# SAM_E54_Xplained_Pro_Memory.net
KiCad netlist of a schematic drawn in Altium Designer
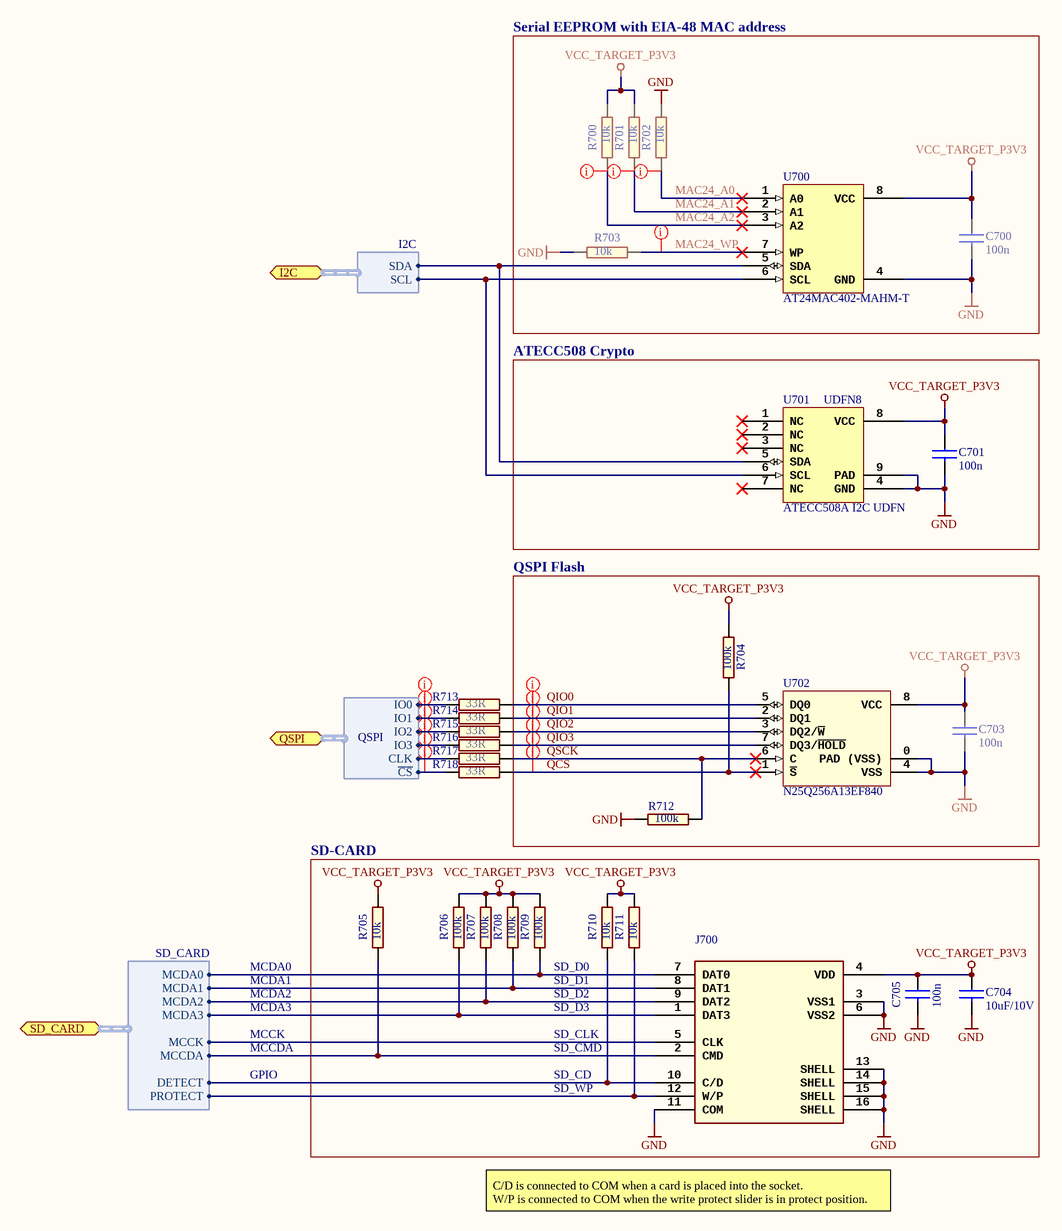
[diagram p0: SAM_E54_Xplained_Pro_Memory.SchDoc]

(export (version "E")
  (design (tool "Eeschema 10.0.6"))
  (components
    (comp (ref "C700")
      (value "100n")
      (footprint "AP1-00053")
      (description "Ceramic capacitor, SMD 0402, X7R, 16V, +/-10%")
      (fields (field (name "TOLERANCE") "16V, +/-10%") (field (name "MANUFACTURER") "Kemet"))
      (libsource (lib "AltiumDbLib") (part "CAP-NONPOL"))
    )
    (comp (ref "C701")
      (value "100n")
      (footprint "AP1-00053")
      (description "Ceramic capacitor, SMD 0402, X7R, 16V, +/-10%")
      (fields (field (name "TOLERANCE") "16V, +/-10%") (field (name "MANUFACTURER") "Kemet"))
      (libsource (lib "AltiumDbLib") (part "CAP-NONPOL"))
    )
    (comp (ref "C703")
      (value "100n")
      (footprint "AP1-00053")
      (description "Ceramic capacitor, SMD 0402, X7R, 16V, +/-10%")
      (fields (field (name "TOLERANCE") "16V, +/-10%") (field (name "MANUFACTURER") "Kemet"))
      (libsource (lib "AltiumDbLib") (part "CAP-NONPOL"))
    )
    (comp (ref "C704")
      (value "10uF/10V")
      (footprint "AP1-00117")
      (description "Ceramic capacitor, SMD 0603, X5R, 10V, 10UF Â± 20%")
      (fields (field (name "MANUFACTURER") "AVX") (field (name "MPN") "0603ZD106MAT2A"))
      (libsource (lib "AltiumDbLib") (part "CAP-NONPOL"))
    )
    (comp (ref "C705")
      (value "100n")
      (footprint "AP1-00053")
      (description "Ceramic capacitor, SMD 0402, X7R, 16V, +/-10%")
      (fields (field (name "TOLERANCE") "16V, +/-10%") (field (name "MANUFACTURER") "Kemet"))
      (libsource (lib "AltiumDbLib") (part "CAP-NONPOL"))
    )
    (comp (ref "J700")
      (value "~")
      (footprint "AP8-00377")
      (description "SD/MMC socket, 2.7mm, push-push, SMD")
      (fields
        (field (name "MANUFACTURER") "Kyocera-elco")
        (field (name "MPN") "KYOCERA - 14 5738 009 220 859+")
      )
      (libsource (lib "AltiumDbLib") (part "SD_MMC"))
    )
    (comp (ref "R700")
      (value "10k")
      (footprint "AP2-00011")
      (description "Thick film resistor, SMD 0402, 1/16W, 1%")
      (fields (field (name "TOLERANCE") "1 %") (field (name "MANUFACTURER") "vishay"))
      (libsource (lib "") (part "R2_1"))
    )
    (comp (ref "R701")
      (value "10k")
      (footprint "AP2-00011")
      (description "Thick film resistor, SMD 0402, 1/16W, 1%")
      (fields (field (name "TOLERANCE") "1 %") (field (name "MANUFACTURER") "vishay"))
      (libsource (lib "") (part "R2_1"))
    )
    (comp (ref "R702")
      (value "10k")
      (footprint "AP2-00011")
      (description "Thick film resistor, SMD 0402, 1/16W, 1%")
      (fields (field (name "TOLERANCE") "1 %") (field (name "MANUFACTURER") "vishay"))
      (libsource (lib "") (part "R2_1"))
    )
    (comp (ref "R703")
      (value "10k")
      (footprint "AP2-00011")
      (description "Thick film resistor, SMD 0402, 1/16W, 1%")
      (fields (field (name "TOLERANCE") "1 %") (field (name "MANUFACTURER") "vishay"))
      (libsource (lib "") (part "R2_2"))
    )
    (comp (ref "R704")
      (value "100k")
      (footprint "AP2-00011")
      (description "Thick film resistor, SMD 0402, 1/16W, 1%")
      (fields (field (name "TOLERANCE") "1 %") (field (name "MANUFACTURER") "ASJ"))
      (libsource (lib "") (part "R2_1"))
    )
    (comp (ref "R705")
      (value "10k")
      (footprint "AP2-00011")
      (description "Thick film resistor, SMD 0402, 1/16W, 1%")
      (fields (field (name "TOLERANCE") "1 %") (field (name "MANUFACTURER") "vishay"))
      (libsource (lib "") (part "R2_1"))
    )
    (comp (ref "R706")
      (value "100k")
      (footprint "AP2-00011")
      (description "Thick film resistor, SMD 0402, 1/16W, 1%")
      (fields (field (name "TOLERANCE") "1 %") (field (name "MANUFACTURER") "ASJ"))
      (libsource (lib "") (part "R2_1"))
    )
    (comp (ref "R707")
      (value "100k")
      (footprint "AP2-00011")
      (description "Thick film resistor, SMD 0402, 1/16W, 1%")
      (fields (field (name "TOLERANCE") "1 %") (field (name "MANUFACTURER") "ASJ"))
      (libsource (lib "") (part "R2_1"))
    )
    (comp (ref "R708")
      (value "100k")
      (footprint "AP2-00011")
      (description "Thick film resistor, SMD 0402, 1/16W, 1%")
      (fields (field (name "TOLERANCE") "1 %") (field (name "MANUFACTURER") "ASJ"))
      (libsource (lib "") (part "R2_1"))
    )
    (comp (ref "R709")
      (value "100k")
      (footprint "AP2-00011")
      (description "Thick film resistor, SMD 0402, 1/16W, 1%")
      (fields (field (name "TOLERANCE") "1 %") (field (name "MANUFACTURER") "ASJ"))
      (libsource (lib "") (part "R2_1"))
    )
    (comp (ref "R710")
      (value "10k")
      (footprint "AP2-00011")
      (description "Thick film resistor, SMD 0402, 1/16W, 1%")
      (fields (field (name "TOLERANCE") "1 %") (field (name "MANUFACTURER") "vishay"))
      (libsource (lib "") (part "R2_1"))
    )
    (comp (ref "R711")
      (value "10k")
      (footprint "AP2-00011")
      (description "Thick film resistor, SMD 0402, 1/16W, 1%")
      (fields (field (name "TOLERANCE") "1 %") (field (name "MANUFACTURER") "vishay"))
      (libsource (lib "") (part "R2_1"))
    )
    (comp (ref "R712")
      (value "100k")
      (footprint "AP2-00011")
      (description "Thick film resistor, SMD 0402, 1/16W, 1%")
      (fields (field (name "TOLERANCE") "1 %") (field (name "MANUFACTURER") "ASJ"))
      (libsource (lib "") (part "R2_2"))
    )
    (comp (ref "R713")
      (value "33R")
      (footprint "AP2-00011")
      (description "Thick film resistor, SMD 0402, 1/16W, 1%")
      (fields (field (name "TOLERANCE") "1 %") (field (name "MANUFACTURER") "ASJ"))
      (libsource (lib "AltiumDbLib") (part "R2"))
    )
    (comp (ref "R714")
      (value "33R")
      (footprint "AP2-00011")
      (description "Thick film resistor, SMD 0402, 1/16W, 1%")
      (fields (field (name "TOLERANCE") "1 %") (field (name "MANUFACTURER") "ASJ"))
      (libsource (lib "AltiumDbLib") (part "R2"))
    )
    (comp (ref "R715")
      (value "33R")
      (footprint "AP2-00011")
      (description "Thick film resistor, SMD 0402, 1/16W, 1%")
      (fields (field (name "TOLERANCE") "1 %") (field (name "MANUFACTURER") "ASJ"))
      (libsource (lib "AltiumDbLib") (part "R2"))
    )
    (comp (ref "R716")
      (value "33R")
      (footprint "AP2-00011")
      (description "Thick film resistor, SMD 0402, 1/16W, 1%")
      (fields (field (name "TOLERANCE") "1 %") (field (name "MANUFACTURER") "ASJ"))
      (libsource (lib "AltiumDbLib") (part "R2"))
    )
    (comp (ref "R717")
      (value "33R")
      (footprint "AP2-00011")
      (description "Thick film resistor, SMD 0402, 1/16W, 1%")
      (fields (field (name "TOLERANCE") "1 %") (field (name "MANUFACTURER") "ASJ"))
      (libsource (lib "AltiumDbLib") (part "R2"))
    )
    (comp (ref "R718")
      (value "33R")
      (footprint "AP2-00011")
      (description "Thick film resistor, SMD 0402, 1/16W, 1%")
      (fields (field (name "TOLERANCE") "1 %") (field (name "MANUFACTURER") "ASJ"))
      (libsource (lib "AltiumDbLib") (part "R2"))
    )
    (comp (ref "U700")
      (value "AT24MAC402-MAHM-T")
      (footprint "AP6-00186")
      (description "2kbit I2C EEPROM, single EUI-48 MAC, 1.7-5.5V, 2x3mm UDFN (8MA2)")
      (fields (field (name "MANUFACTURER") "ATMEL"))
      (libsource (lib "AltiumDbLib") (part "AT24MAC-8PIN"))
    )
    (comp (ref "U701")
      (value "ATECC508A I2C UDFN")
      (footprint "AP6-00409")
      (description "ATECC508A with an I2C Interface and a 8 Pin UDFN Package with Paddle")
      (fields (field (name "MANUFACTURER") "MICROCHIP") (field (name "MPN") "ATECC508A-MAHDA-T"))
      (libsource (lib "AltiumDbLib") (part "ATECC508A_I2C_UDFN"))
    )
    (comp (ref "U702")
      (value "N25Q256A13EF840")
      (footprint "AP6-00478")
      (description "256 Mbit (32MB) QSPI flash, 3.3V, 108MHz, V-PDFN-8 (8x6mm)")
      (fields (field (name "MANUFACTURER") "Micron") (field (name "MPN") "N25Q256A13EF840F"))
      (libsource (lib "AltiumDbLib") (part "N25Q256A1"))
    )
  )
  (nets
    (net (code "4") (name "/CLK") (class "Default")
      (node (ref "R717") (pin "2") (pinfunction "2_2") (pintype "passive"))
    )
    (net (code "5") (name "/DETECT") (class "Default")
      (node (ref "J700") (pin "10") (pinfunction "C/D_10") (pintype "passive"))
      (node (ref "R710") (pin "1") (pinfunction "1_1") (pintype "passive"))
    )
    (net (code "6") (name "/IO0") (class "Default")
      (node (ref "R713") (pin "2") (pinfunction "2_2") (pintype "passive"))
    )
    (net (code "7") (name "/IO1") (class "Default")
      (node (ref "R714") (pin "2") (pinfunction "2_2") (pintype "passive"))
    )
    (net (code "8") (name "/IO2") (class "Default")
      (node (ref "R715") (pin "2") (pinfunction "2_2") (pintype "passive"))
    )
    (net (code "9") (name "/IO3") (class "Default")
      (node (ref "R716") (pin "2") (pinfunction "2_2") (pintype "passive"))
    )
    (net (code "10") (name "/MAC24_A0") (class "Default")
      (node (ref "R702") (pin "1") (pinfunction "1_1") (pintype "passive"))
      (node (ref "U700") (pin "1") (pinfunction "A0_1") (pintype "input"))
    )
    (net (code "11") (name "/MAC24_A1") (class "Default")
      (node (ref "R701") (pin "1") (pinfunction "1_1") (pintype "passive"))
      (node (ref "U700") (pin "2") (pinfunction "A1_2") (pintype "input"))
    )
    (net (code "12") (name "/MAC24_A2") (class "Default")
      (node (ref "R700") (pin "1") (pinfunction "1_1") (pintype "passive"))
      (node (ref "U700") (pin "3") (pinfunction "A2_3") (pintype "input"))
    )
    (net (code "13") (name "/MAC24_WP") (class "Default")
      (node (ref "R703") (pin "2") (pinfunction "2_2") (pintype "passive"))
      (node (ref "U700") (pin "7") (pinfunction "WP_7") (pintype "input"))
    )
    (net (code "14") (name "/MCCDA") (class "Default")
      (node (ref "J700") (pin "2") (pinfunction "CMD_2") (pintype "passive"))
      (node (ref "R705") (pin "1") (pinfunction "1_1") (pintype "passive"))
    )
    (net (code "15") (name "/MCCK") (class "Default")
      (node (ref "J700") (pin "5") (pinfunction "CLK_5") (pintype "passive"))
    )
    (net (code "16") (name "/MCDA0") (class "Default")
      (node (ref "J700") (pin "7") (pinfunction "DAT0_7") (pintype "passive"))
      (node (ref "R709") (pin "1") (pinfunction "1_1") (pintype "passive"))
    )
    (net (code "17") (name "/MCDA1") (class "Default")
      (node (ref "J700") (pin "8") (pinfunction "DAT1_8") (pintype "passive"))
      (node (ref "R708") (pin "1") (pinfunction "1_1") (pintype "passive"))
    )
    (net (code "18") (name "/MCDA2") (class "Default")
      (node (ref "J700") (pin "9") (pinfunction "DAT2_9") (pintype "passive"))
      (node (ref "R707") (pin "1") (pinfunction "1_1") (pintype "passive"))
    )
    (net (code "19") (name "/MCDA3") (class "Default")
      (node (ref "J700") (pin "1") (pinfunction "DAT3_1") (pintype "passive"))
      (node (ref "R706") (pin "1") (pinfunction "1_1") (pintype "passive"))
    )
    (net (code "20") (name "/PROTECT") (class "Default")
      (node (ref "J700") (pin "12") (pinfunction "W/P_12") (pintype "passive"))
      (node (ref "R711") (pin "1") (pinfunction "1_1") (pintype "passive"))
    )
    (net (code "21") (name "/QCS") (class "Default")
      (node (ref "R704") (pin "1") (pinfunction "1_1") (pintype "passive"))
      (node (ref "R718") (pin "1") (pinfunction "1_1") (pintype "passive"))
      (node (ref "U702") (pin "1") (pinfunction "~{S}_1") (pintype "input"))
    )
    (net (code "22") (name "/QIO0") (class "Default")
      (node (ref "R713") (pin "1") (pinfunction "1_1") (pintype "passive"))
      (node (ref "U702") (pin "5") (pinfunction "DQ0_5") (pintype "bidirectional"))
    )
    (net (code "23") (name "/QIO1") (class "Default")
      (node (ref "R714") (pin "1") (pinfunction "1_1") (pintype "passive"))
      (node (ref "U702") (pin "2") (pinfunction "DQ1_2") (pintype "bidirectional"))
    )
    (net (code "24") (name "/QIO2") (class "Default")
      (node (ref "R715") (pin "1") (pinfunction "1_1") (pintype "passive"))
      (node (ref "U702") (pin "3") (pinfunction "DQ2/~{W}_3") (pintype "bidirectional"))
    )
    (net (code "25") (name "/QIO3") (class "Default")
      (node (ref "R716") (pin "1") (pinfunction "1_1") (pintype "passive"))
      (node (ref "U702") (pin "7") (pinfunction "DQ3/~{HOLD}_7") (pintype "bidirectional"))
    )
    (net (code "26") (name "/QSCK") (class "Default")
      (node (ref "R712") (pin "2") (pinfunction "2_2") (pintype "passive"))
      (node (ref "R717") (pin "1") (pinfunction "1_1") (pintype "passive"))
      (node (ref "U702") (pin "6") (pinfunction "C_6") (pintype "input"))
    )
    (net (code "27") (name "/SCL") (class "Default")
      (node (ref "U700") (pin "6") (pinfunction "SCL_6") (pintype "input"))
      (node (ref "U701") (pin "6") (pinfunction "SCL_6") (pintype "input"))
    )
    (net (code "28") (name "/SDA") (class "Default")
      (node (ref "U700") (pin "5") (pinfunction "SDA_5") (pintype "bidirectional"))
      (node (ref "U701") (pin "5") (pinfunction "SDA_5") (pintype "bidirectional"))
    )
    (net (code "32") (name "/~{CS}") (class "Default")
      (node (ref "R718") (pin "2") (pinfunction "2_2") (pintype "passive"))
    )
    (net (code "33") (name "GND") (class "Default")
      (node (ref "C700") (pin "2") (pinfunction "2_2") (pintype "passive"))
      (node (ref "C701") (pin "2") (pinfunction "2_2") (pintype "passive"))
      (node (ref "C703") (pin "2") (pinfunction "2_2") (pintype "passive"))
      (node (ref "C704") (pin "2") (pinfunction "2_2") (pintype "passive"))
      (node (ref "C705") (pin "2") (pinfunction "2_2") (pintype "passive"))
      (node (ref "J700") (pin "11") (pinfunction "COM_11") (pintype "passive"))
      (node (ref "J700") (pin "13") (pinfunction "SHELL_13") (pintype "passive"))
      (node (ref "J700") (pin "14") (pinfunction "SHELL_14") (pintype "passive"))
      (node (ref "J700") (pin "15") (pinfunction "SHELL_15") (pintype "passive"))
      (node (ref "J700") (pin "16") (pinfunction "SHELL_16") (pintype "passive"))
      (node (ref "J700") (pin "3") (pinfunction "VSS1_3") (pintype "passive"))
      (node (ref "J700") (pin "6") (pinfunction "VSS2_6") (pintype "passive"))
      (node (ref "R702") (pin "2") (pinfunction "2_2") (pintype "passive"))
      (node (ref "R703") (pin "1") (pinfunction "1_1") (pintype "passive"))
      (node (ref "R712") (pin "1") (pinfunction "1_1") (pintype "passive"))
      (node (ref "U700") (pin "4") (pinfunction "GND_4") (pintype "power_in"))
      (node (ref "U701") (pin "4") (pinfunction "GND_4") (pintype "power_in"))
      (node (ref "U701") (pin "9") (pinfunction "PAD_9") (pintype "power_in"))
      (node (ref "U702") (pin "0") (pinfunction "PAD_(VSS)_0") (pintype "power_in"))
      (node (ref "U702") (pin "4") (pinfunction "VSS_4") (pintype "power_in"))
    )
    (net (code "34") (name "VCC_TARGET_P3V3") (class "Default")
      (node (ref "C700") (pin "1") (pinfunction "1_1") (pintype "passive"))
      (node (ref "C701") (pin "1") (pinfunction "1_1") (pintype "passive"))
      (node (ref "C703") (pin "1") (pinfunction "1_1") (pintype "passive"))
      (node (ref "C704") (pin "1") (pinfunction "1_1") (pintype "passive"))
      (node (ref "C705") (pin "1") (pinfunction "1_1") (pintype "passive"))
      (node (ref "J700") (pin "4") (pinfunction "VDD_4") (pintype "passive"))
      (node (ref "R700") (pin "2") (pinfunction "2_2") (pintype "passive"))
      (node (ref "R701") (pin "2") (pinfunction "2_2") (pintype "passive"))
      (node (ref "R704") (pin "2") (pinfunction "2_2") (pintype "passive"))
      (node (ref "R705") (pin "2") (pinfunction "2_2") (pintype "passive"))
      (node (ref "R706") (pin "2") (pinfunction "2_2") (pintype "passive"))
      (node (ref "R707") (pin "2") (pinfunction "2_2") (pintype "passive"))
      (node (ref "R708") (pin "2") (pinfunction "2_2") (pintype "passive"))
      (node (ref "R709") (pin "2") (pinfunction "2_2") (pintype "passive"))
      (node (ref "R710") (pin "2") (pinfunction "2_2") (pintype "passive"))
      (node (ref "R711") (pin "2") (pinfunction "2_2") (pintype "passive"))
      (node (ref "U700") (pin "8") (pinfunction "VCC_8") (pintype "power_in"))
      (node (ref "U701") (pin "8") (pinfunction "VCC_8") (pintype "power_in"))
      (node (ref "U702") (pin "8") (pinfunction "VCC_8") (pintype "power_in"))
    )
    (net (code "35") (name "unconnected-(U701-NC-Pad1)") (class "Default")
      (node (ref "U701") (pin "1") (pinfunction "NC_1") (pintype "passive+no_connect"))
    )
    (net (code "36") (name "unconnected-(U701-NC-Pad2)") (class "Default")
      (node (ref "U701") (pin "2") (pinfunction "NC_2") (pintype "passive+no_connect"))
    )
    (net (code "37") (name "unconnected-(U701-NC-Pad3)") (class "Default")
      (node (ref "U701") (pin "3") (pinfunction "NC_3") (pintype "passive+no_connect"))
    )
    (net (code "38") (name "unconnected-(U701-NC-Pad7)") (class "Default")
      (node (ref "U701") (pin "7") (pinfunction "NC_7") (pintype "passive+no_connect"))
    )
  )
)
